# PA_classD.net
KiCad netlist of a schematic drawn in Altium Designer
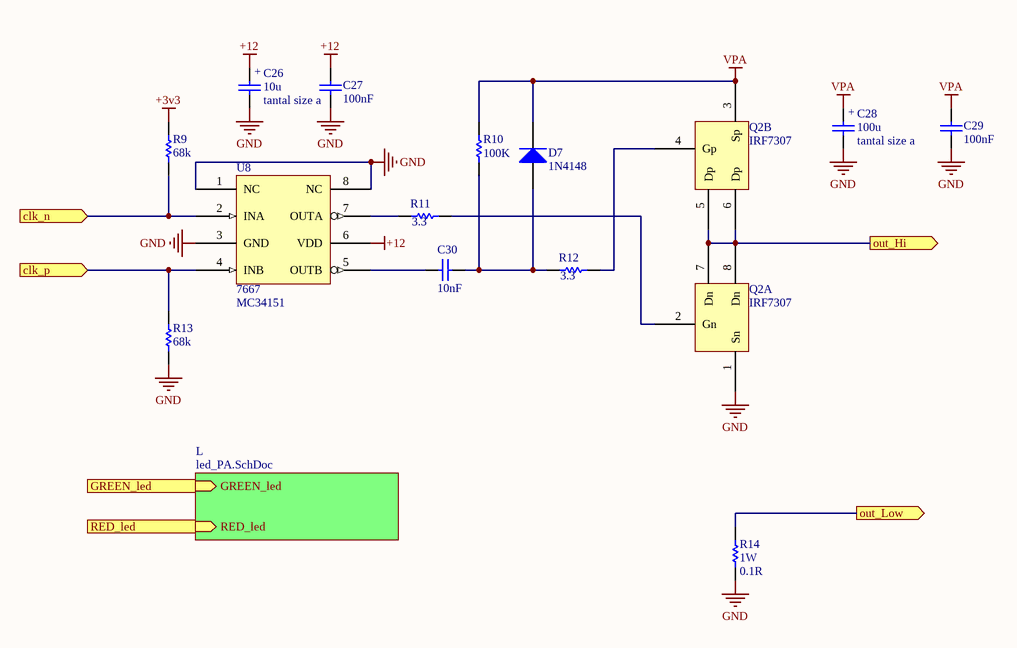
[diagram p0: PA_classD.SchDoc]

(export (version "E")
  (design (tool "Eeschema 10.0.6"))
  (components
    (comp (ref "C26")
      (value "tantal size a")
      (footprint "CAPP 1206 (3216X18L) Size A")
      (fields (field (name "ALTIUM_VALUE") "10u"))
      (libsource (lib "Altium library (www.AVRelec.com)") (part "Cap Pol"))
    )
    (comp (ref "C27")
      (value "100nF")
      (footprint "SMD_CAP_0805")
      (description "CAP-100Nf")
      (fields (field (name "Comment") "Cap"))
      (libsource (lib "Altium library (www.AVRelec.com)") (part "Cap ceramic"))
    )
    (comp (ref "C28")
      (value "tantal size a")
      (footprint "CAPP 1206 (3216X18L) Size A")
      (fields (field (name "ALTIUM_VALUE") "100u"))
      (libsource (lib "Altium library (www.AVRelec.com)") (part "Cap Pol"))
    )
    (comp (ref "C29")
      (value "100nF")
      (footprint "SMD_CAP_0805")
      (description "CAP-100Nf")
      (fields (field (name "Comment") "Cap"))
      (libsource (lib "Altium library (www.AVRelec.com)") (part "Cap ceramic"))
    )
    (comp (ref "C30")
      (value "10nF")
      (footprint "SMD_CAP_0805")
      (description "CAP-100Nf")
      (fields (field (name "Comment") "Cap"))
      (libsource (lib "Altium library (www.AVRelec.com)") (part "Cap ceramic"))
    )
    (comp (ref "D7")
      (value "1N4148")
      (footprint "LL4148")
      (description "High Conductance Fast Diode")
      (fields (field (name "PUBLISHER") "Altium Limited"))
      (libsource (lib "Miscellaneous Devices") (part "Diode 1N4148"))
    )
    (comp (ref "Q2")
      (value "IRF7307")
      (footprint "Miscellaneous Devices:SO8_M")
      (libsource (lib "PA_sch") (part "IRF7106"))
    )
    (comp (ref "R9")
      (value "68k")
      (footprint "RES 0805 (2012X06L)")
      (description "Resistor")
      (fields (field (name "Comment") "Res1") (field (name "PUBLISHER") "Altium Limited"))
      (libsource (lib "Miscellaneous Devices") (part "Res1"))
    )
    (comp (ref "R10")
      (value "100K")
      (footprint "RES 0805 (2012X06L)")
      (description "Resistor")
      (fields (field (name "Comment") "Res1") (field (name "PUBLISHER") "Altium Limited"))
      (libsource (lib "Miscellaneous Devices") (part "Res1"))
    )
    (comp (ref "R11")
      (value "3.3")
      (footprint "RES 0805 (2012X06L)")
      (description "Resistor")
      (fields (field (name "Comment") "Res1") (field (name "PUBLISHER") "Altium Limited"))
      (libsource (lib "Miscellaneous Devices") (part "Res1"))
    )
    (comp (ref "R12")
      (value "3.3")
      (footprint "RES 0805 (2012X06L)")
      (description "Resistor")
      (fields (field (name "Comment") "Res1") (field (name "PUBLISHER") "Altium Limited"))
      (libsource (lib "Miscellaneous Devices") (part "Res1"))
    )
    (comp (ref "R13")
      (value "68k")
      (footprint "RES 0805 (2012X06L)")
      (description "Resistor")
      (fields (field (name "Comment") "Res1") (field (name "PUBLISHER") "Altium Limited"))
      (libsource (lib "Miscellaneous Devices") (part "Res1"))
    )
    (comp (ref "R14")
      (value "1W")
      (footprint "Axial 1W  7_0mm")
      (description "Resistor")
      (fields (field (name "ALTIUM_VALUE") "0.1R") (field (name "PUBLISHER") "Altium Limited"))
      (libsource (lib "Miscellaneous Devices") (part "Res1"))
    )
    (comp (ref "U8")
      (value "7667")
      (footprint "Miscellaneous Devices:SO8_M")
      (libsource (lib "PA_sch") (part "ICL7667"))
    )
  )
  (nets
    (net (code "1") (name "+3v3") (class "Default")
      (node (ref "R9") (pin "1") (pinfunction "1_1") (pintype "passive"))
    )
    (net (code "2") (name "+12") (class "Default")
      (node (ref "C26") (pin "+") (pinfunction "+_+") (pintype "passive"))
      (node (ref "C27") (pin "1") (pinfunction "1_1") (pintype "passive"))
      (node (ref "U8") (pin "6") (pinfunction "VDD_6") (pintype "power_in"))
    )
    (net (code "5") (name "/clk_n") (class "Default")
      (node (ref "R9") (pin "2") (pinfunction "2_2") (pintype "passive"))
      (node (ref "U8") (pin "2") (pinfunction "INA_2") (pintype "input"))
    )
    (net (code "6") (name "/clk_p") (class "Default")
      (node (ref "R13") (pin "1") (pinfunction "1_1") (pintype "passive"))
      (node (ref "U8") (pin "4") (pinfunction "INB_4") (pintype "input"))
    )
    (net (code "7") (name "/out_Hi") (class "Default")
      (node (ref "Q2") (pin "5") (pinfunction "Dp_5") (pintype "passive"))
      (node (ref "Q2") (pin "6") (pinfunction "Dp_6") (pintype "passive"))
      (node (ref "Q2") (pin "7") (pinfunction "Dn_7") (pintype "passive"))
      (node (ref "Q2") (pin "8") (pinfunction "Dn_8") (pintype "passive"))
    )
    (net (code "8") (name "/out_Low") (class "Default")
      (node (ref "R14") (pin "2") (pinfunction "2_2") (pintype "passive"))
    )
    (net (code "9") (name "GND") (class "Default")
      (node (ref "C26") (pin "-") (pinfunction "-_-") (pintype "passive"))
      (node (ref "C27") (pin "2") (pinfunction "2_2") (pintype "passive"))
      (node (ref "C28") (pin "-") (pinfunction "-_-") (pintype "passive"))
      (node (ref "C29") (pin "2") (pinfunction "2_2") (pintype "passive"))
      (node (ref "Q2") (pin "1") (pinfunction "Sn_1") (pintype "passive"))
      (node (ref "R13") (pin "2") (pinfunction "2_2") (pintype "passive"))
      (node (ref "R14") (pin "1") (pinfunction "1_1") (pintype "passive"))
      (node (ref "U8") (pin "1") (pinfunction "NC_1") (pintype "passive"))
      (node (ref "U8") (pin "3") (pinfunction "GND_3") (pintype "power_in"))
      (node (ref "U8") (pin "8") (pinfunction "NC_8") (pintype "passive"))
    )
    (net (code "10") (name "Net-(D7-A)") (class "Default")
      (node (ref "C30") (pin "2") (pinfunction "2_2") (pintype "passive"))
      (node (ref "D7") (pin "1") (pinfunction "A_1") (pintype "passive"))
      (node (ref "R10") (pin "2") (pinfunction "2_2") (pintype "passive"))
      (node (ref "R12") (pin "2") (pinfunction "2_2") (pintype "passive"))
    )
    (net (code "11") (name "Net-(Q2A-Gn)") (class "Default")
      (node (ref "Q2") (pin "2") (pinfunction "Gn_2") (pintype "passive"))
      (node (ref "R11") (pin "1") (pinfunction "1_1") (pintype "passive"))
    )
    (net (code "12") (name "Net-(Q2B-Gp)") (class "Default")
      (node (ref "Q2") (pin "4") (pinfunction "Gp_4") (pintype "passive"))
      (node (ref "R12") (pin "1") (pinfunction "1_1") (pintype "passive"))
    )
    (net (code "13") (name "Net-(U8-OUTA)") (class "Default")
      (node (ref "R11") (pin "2") (pinfunction "2_2") (pintype "passive"))
      (node (ref "U8") (pin "7") (pinfunction "OUTA_7") (pintype "output"))
    )
    (net (code "14") (name "Net-(U8-OUTB)") (class "Default")
      (node (ref "C30") (pin "1") (pinfunction "1_1") (pintype "passive"))
      (node (ref "U8") (pin "5") (pinfunction "OUTB_5") (pintype "output"))
    )
    (net (code "15") (name "VPA") (class "Default")
      (node (ref "C28") (pin "+") (pinfunction "+_+") (pintype "passive"))
      (node (ref "C29") (pin "1") (pinfunction "1_1") (pintype "passive"))
      (node (ref "D7") (pin "2") (pinfunction "K_2") (pintype "passive"))
      (node (ref "Q2") (pin "3") (pinfunction "Sp_3") (pintype "passive"))
      (node (ref "R10") (pin "1") (pinfunction "1_1") (pintype "passive"))
    )
  )
)
